# cpu.net
KiCad netlist of a schematic drawn in Altium Designer
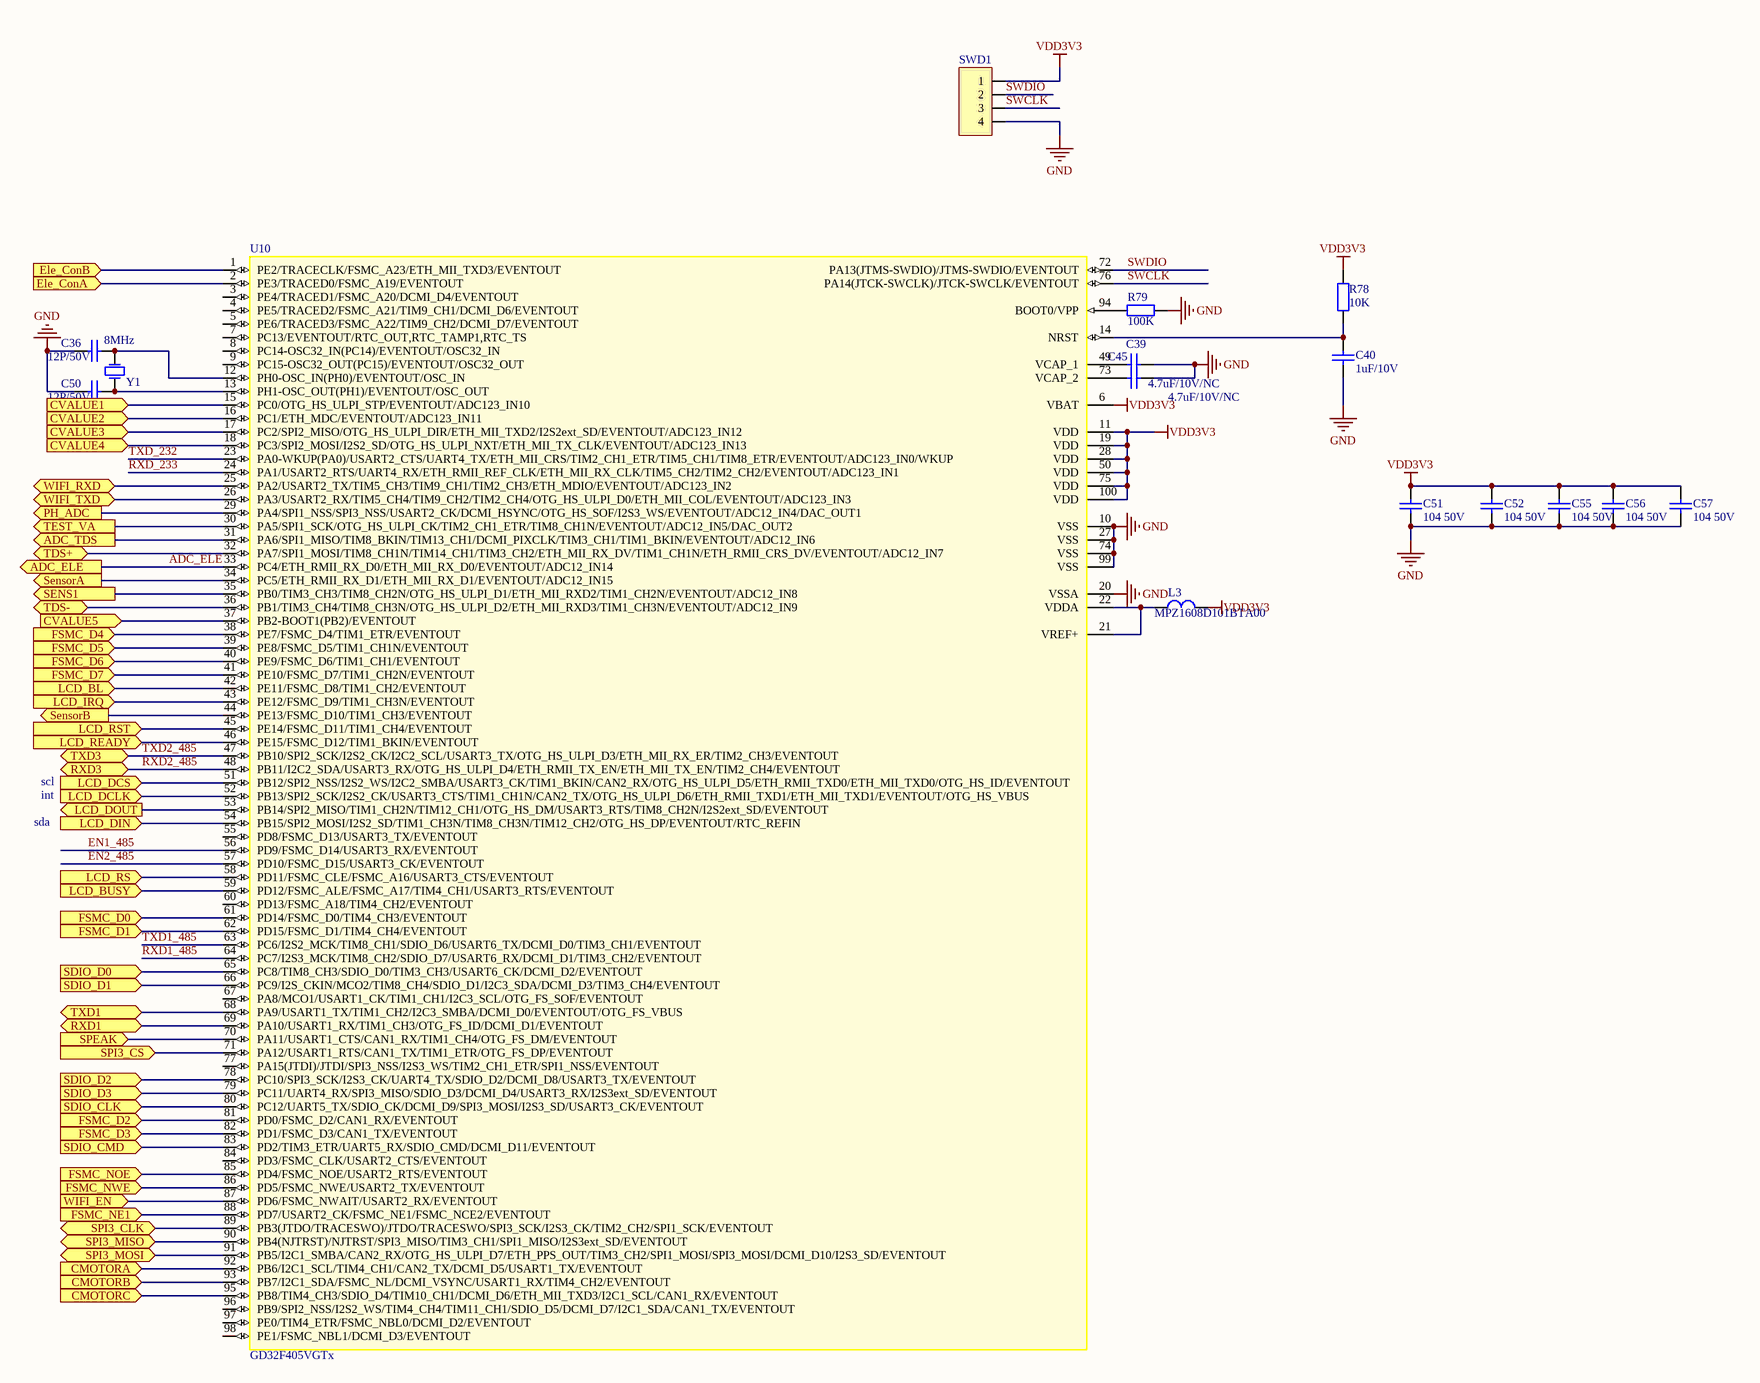
[diagram p0: cpu.SchDoc]

(export (version "E")
  (design (tool "Eeschema 10.0.6"))
  (components
    (comp (ref "C36")
      (value "12P/50V")
      (footprint "SMD-0603C")
      (description "贴片电容 5%")
      (libsource (lib "XiaoyI") (part "CAP4"))
    )
    (comp (ref "C39")
      (value "4.7uF/10V/NC")
      (footprint "SMD-0603C")
      (description "贴片电容 20%")
      (libsource (lib "XiaoyI") (part "CAP4"))
    )
    (comp (ref "C40")
      (value "1uF/10V")
      (footprint "SMD-0603C")
      (description "贴片电容 20%")
      (libsource (lib "XiaoyI") (part "CAP4"))
    )
    (comp (ref "C45")
      (value "4.7uF/10V/NC")
      (footprint "SMD-0603C")
      (description "贴片电容 20%")
      (libsource (lib "XiaoyI") (part "CAP4"))
    )
    (comp (ref "C50")
      (value "12P/50V")
      (footprint "SMD-0603C")
      (description "贴片电容 5%")
      (libsource (lib "XiaoyI") (part "CAP4"))
    )
    (comp (ref "C51")
      (value "104 50V")
      (footprint "SMD-0603C")
      (description "贴片电容 20%")
      (libsource (lib "XiaoyI") (part "CAP4"))
    )
    (comp (ref "C52")
      (value "104 50V")
      (footprint "SMD-0603C")
      (description "贴片电容 20%")
      (libsource (lib "XiaoyI") (part "CAP4"))
    )
    (comp (ref "C55")
      (value "104 50V")
      (footprint "SMD-0603C")
      (description "贴片电容 20%")
      (libsource (lib "XiaoyI") (part "CAP4"))
    )
    (comp (ref "C56")
      (value "104 50V")
      (footprint "SMD-0603C")
      (description "贴片电容 20%")
      (libsource (lib "XiaoyI") (part "CAP4"))
    )
    (comp (ref "C57")
      (value "104 50V")
      (footprint "SMD-0603C")
      (description "贴片电容 20%")
      (libsource (lib "XiaoyI") (part "CAP4"))
    )
    (comp (ref "L3")
      (value "MPZ1608D101BTA00")
      (footprint "SMD-0603")
      (description "磁珠电感 100R 100MHz")
      (libsource (lib "XiaoyI") (part "CIZHU1"))
    )
    (comp (ref "R78")
      (value "10K")
      (footprint "SMD-0603")
      (description "贴片电阻 5%")
      (libsource (lib "XiaoyI") (part "RES2"))
    )
    (comp (ref "R79")
      (value "100K")
      (footprint "SMD-0603")
      (description "贴片电阻 5%")
      (libsource (lib "") (part "RES2_1"))
    )
    (comp (ref "SWD1")
      (value "SIP-4 (NC)")
      (footprint "SIP-4")
      (description "ISP 下载")
      (libsource (lib "XiaoyI") (part "SIP-4"))
    )
    (comp (ref "U10")
      (value "GD32F405VGTx")
      (footprint "STM-LQFP100_N")
      (fields (field (name "MANUFACTURER") "STMicroelectronics") (field (name "PARTNUMBER") "STM32F405VGT6"))
      (libsource (lib "STM32F4") (part "STM32F405VGTx"))
    )
    (comp (ref "Y1")
      (value "8MHz")
      (footprint "XTAL-3225-2")
      (description "3225 贴片晶振")
      (libsource (lib "XiaoyI") (part "XTAL"))
    )
  )
  (nets
    (net (code "1") (name "/ADC_ELE") (class "Default")
      (node (ref "U10") (pin "33") (pinfunction "PC4/ETH_RMII_RX_D0/ETH_MII_RX_D0/EVENTOUT/ADC12_IN14_33") (pintype "bidirectional"))
    )
    (net (code "2") (name "/ADC_TDS") (class "Default")
      (node (ref "U10") (pin "31") (pinfunction "PA6/SPI1_MISO/TIM8_BKIN/TIM13_CH1/DCMI_PIXCLK/TIM3_CH1/TIM1_BKIN/EVENTOUT/ADC12_IN6_31") (pintype "bidirectional"))
    )
    (net (code "3") (name "/CMOTORA") (class "Default")
      (node (ref "U10") (pin "92") (pinfunction "PB6/I2C1_SCL/TIM4_CH1/CAN2_TX/DCMI_D5/USART1_TX/EVENTOUT_92") (pintype "bidirectional"))
    )
    (net (code "4") (name "/CMOTORB") (class "Default")
      (node (ref "U10") (pin "93") (pinfunction "PB7/I2C1_SDA/FSMC_NL/DCMI_VSYNC/USART1_RX/TIM4_CH2/EVENTOUT_93") (pintype "bidirectional"))
    )
    (net (code "5") (name "/CMOTORC") (class "Default")
      (node (ref "U10") (pin "95") (pinfunction "PB8/TIM4_CH3/SDIO_D4/TIM10_CH1/DCMI_D6/ETH_MII_TXD3/I2C1_SCL/CAN1_RX/EVENTOUT_95") (pintype "bidirectional"))
    )
    (net (code "6") (name "/CVALUE1") (class "Default")
      (node (ref "U10") (pin "15") (pinfunction "PC0/OTG_HS_ULPI_STP/EVENTOUT/ADC123_IN10_15") (pintype "bidirectional"))
    )
    (net (code "7") (name "/CVALUE2") (class "Default")
      (node (ref "U10") (pin "16") (pinfunction "PC1/ETH_MDC/EVENTOUT/ADC123_IN11_16") (pintype "bidirectional"))
    )
    (net (code "8") (name "/CVALUE3") (class "Default")
      (node (ref "U10") (pin "17") (pinfunction "PC2/SPI2_MISO/OTG_HS_ULPI_DIR/ETH_MII_TXD2/I2S2ext_SD/EVENTOUT/ADC123_IN12_17") (pintype "bidirectional"))
    )
    (net (code "9") (name "/CVALUE4") (class "Default")
      (node (ref "U10") (pin "18") (pinfunction "PC3/SPI2_MOSI/I2S2_SD/OTG_HS_ULPI_NXT/ETH_MII_TX_CLK/EVENTOUT/ADC123_IN13_18") (pintype "bidirectional"))
    )
    (net (code "10") (name "/CVALUE5") (class "Default")
      (node (ref "U10") (pin "37") (pinfunction "PB2-BOOT1(PB2)/EVENTOUT_37") (pintype "bidirectional"))
    )
    (net (code "11") (name "/EN1_485") (class "Default")
      (node (ref "U10") (pin "56") (pinfunction "PD9/FSMC_D14/USART3_RX/EVENTOUT_56") (pintype "bidirectional"))
    )
    (net (code "12") (name "/EN2_485") (class "Default")
      (node (ref "U10") (pin "57") (pinfunction "PD10/FSMC_D15/USART3_CK/EVENTOUT_57") (pintype "bidirectional"))
    )
    (net (code "13") (name "/Ele_ConA") (class "Default")
      (node (ref "U10") (pin "2") (pinfunction "PE3/TRACED0/FSMC_A19/EVENTOUT_2") (pintype "bidirectional"))
    )
    (net (code "14") (name "/Ele_ConB") (class "Default")
      (node (ref "U10") (pin "1") (pinfunction "PE2/TRACECLK/FSMC_A23/ETH_MII_TXD3/EVENTOUT_1") (pintype "bidirectional"))
    )
    (net (code "15") (name "/FSMC_D0") (class "Default")
      (node (ref "U10") (pin "61") (pinfunction "PD14/FSMC_D0/TIM4_CH3/EVENTOUT_61") (pintype "bidirectional"))
    )
    (net (code "16") (name "/FSMC_D1") (class "Default")
      (node (ref "U10") (pin "62") (pinfunction "PD15/FSMC_D1/TIM4_CH4/EVENTOUT_62") (pintype "bidirectional"))
    )
    (net (code "17") (name "/FSMC_D2") (class "Default")
      (node (ref "U10") (pin "81") (pinfunction "PD0/FSMC_D2/CAN1_RX/EVENTOUT_81") (pintype "bidirectional"))
    )
    (net (code "18") (name "/FSMC_D3") (class "Default")
      (node (ref "U10") (pin "82") (pinfunction "PD1/FSMC_D3/CAN1_TX/EVENTOUT_82") (pintype "bidirectional"))
    )
    (net (code "19") (name "/FSMC_D4") (class "Default")
      (node (ref "U10") (pin "38") (pinfunction "PE7/FSMC_D4/TIM1_ETR/EVENTOUT_38") (pintype "bidirectional"))
    )
    (net (code "20") (name "/FSMC_D5") (class "Default")
      (node (ref "U10") (pin "39") (pinfunction "PE8/FSMC_D5/TIM1_CH1N/EVENTOUT_39") (pintype "bidirectional"))
    )
    (net (code "21") (name "/FSMC_D6") (class "Default")
      (node (ref "U10") (pin "40") (pinfunction "PE9/FSMC_D6/TIM1_CH1/EVENTOUT_40") (pintype "bidirectional"))
    )
    (net (code "22") (name "/FSMC_D7") (class "Default")
      (node (ref "U10") (pin "41") (pinfunction "PE10/FSMC_D7/TIM1_CH2N/EVENTOUT_41") (pintype "bidirectional"))
    )
    (net (code "23") (name "/FSMC_NE1") (class "Default")
      (node (ref "U10") (pin "88") (pinfunction "PD7/USART2_CK/FSMC_NE1/FSMC_NCE2/EVENTOUT_88") (pintype "bidirectional"))
    )
    (net (code "24") (name "/FSMC_NOE") (class "Default")
      (node (ref "U10") (pin "85") (pinfunction "PD4/FSMC_NOE/USART2_RTS/EVENTOUT_85") (pintype "bidirectional"))
    )
    (net (code "25") (name "/FSMC_NWE") (class "Default")
      (node (ref "U10") (pin "86") (pinfunction "PD5/FSMC_NWE/USART2_TX/EVENTOUT_86") (pintype "bidirectional"))
    )
    (net (code "26") (name "/LCD_BL") (class "Default")
      (node (ref "U10") (pin "42") (pinfunction "PE11/FSMC_D8/TIM1_CH2/EVENTOUT_42") (pintype "bidirectional"))
    )
    (net (code "27") (name "/LCD_BUSY") (class "Default")
      (node (ref "U10") (pin "59") (pinfunction "PD12/FSMC_ALE/FSMC_A17/TIM4_CH1/USART3_RTS/EVENTOUT_59") (pintype "bidirectional"))
    )
    (net (code "28") (name "/LCD_DCLK") (class "Default")
      (node (ref "U10") (pin "52") (pinfunction "PB13/SPI2_SCK/I2S2_CK/USART3_CTS/TIM1_CH1N/CAN2_TX/OTG_HS_ULPI_D6/ETH_RMII_TXD1/ETH_MII_TXD1/EVENTOUT/OTG_HS_VBUS_52") (pintype "bidirectional"))
    )
    (net (code "29") (name "/LCD_DCS") (class "Default")
      (node (ref "U10") (pin "51") (pinfunction "PB12/SPI2_NSS/I2S2_WS/I2C2_SMBA/USART3_CK/TIM1_BKIN/CAN2_RX/OTG_HS_ULPI_D5/ETH_RMII_TXD0/ETH_MII_TXD0/OTG_HS_ID/EVENTOUT_51") (pintype "bidirectional"))
    )
    (net (code "30") (name "/LCD_DIN") (class "Default")
      (node (ref "U10") (pin "54") (pinfunction "PB15/SPI2_MOSI/I2S2_SD/TIM1_CH3N/TIM8_CH3N/TIM12_CH2/OTG_HS_DP/EVENTOUT/RTC_REFIN_54") (pintype "bidirectional"))
    )
    (net (code "31") (name "/LCD_DOUT") (class "Default")
      (node (ref "U10") (pin "53") (pinfunction "PB14/SPI2_MISO/TIM1_CH2N/TIM12_CH1/OTG_HS_DM/USART3_RTS/TIM8_CH2N/I2S2ext_SD/EVENTOUT_53") (pintype "bidirectional"))
    )
    (net (code "32") (name "/LCD_IRQ") (class "Default")
      (node (ref "U10") (pin "43") (pinfunction "PE12/FSMC_D9/TIM1_CH3N/EVENTOUT_43") (pintype "bidirectional"))
    )
    (net (code "33") (name "/LCD_READY") (class "Default")
      (node (ref "U10") (pin "46") (pinfunction "PE15/FSMC_D12/TIM1_BKIN/EVENTOUT_46") (pintype "bidirectional"))
    )
    (net (code "34") (name "/LCD_RS") (class "Default")
      (node (ref "U10") (pin "58") (pinfunction "PD11/FSMC_CLE/FSMC_A16/USART3_CTS/EVENTOUT_58") (pintype "bidirectional"))
    )
    (net (code "35") (name "/LCD_RST") (class "Default")
      (node (ref "U10") (pin "45") (pinfunction "PE14/FSMC_D11/TIM1_CH4/EVENTOUT_45") (pintype "bidirectional"))
    )
    (net (code "36") (name "/PH_ADC") (class "Default")
      (node (ref "U10") (pin "29") (pinfunction "PA4/SPI1_NSS/SPI3_NSS/USART2_CK/DCMI_HSYNC/OTG_HS_SOF/I2S3_WS/EVENTOUT/ADC12_IN4/DAC_OUT1_29") (pintype "bidirectional"))
    )
    (net (code "37") (name "/RXD1") (class "Default")
      (node (ref "U10") (pin "69") (pinfunction "PA10/USART1_RX/TIM1_CH3/OTG_FS_ID/DCMI_D1/EVENTOUT_69") (pintype "bidirectional"))
    )
    (net (code "38") (name "/RXD1_485") (class "Default")
      (node (ref "U10") (pin "64") (pinfunction "PC7/I2S3_MCK/TIM8_CH2/SDIO_D7/USART6_RX/DCMI_D1/TIM3_CH2/EVENTOUT_64") (pintype "bidirectional"))
    )
    (net (code "39") (name "/RXD2_485") (class "Default")
      (node (ref "U10") (pin "48") (pinfunction "PB11/I2C2_SDA/USART3_RX/OTG_HS_ULPI_D4/ETH_RMII_TX_EN/ETH_MII_TX_EN/TIM2_CH4/EVENTOUT_48") (pintype "bidirectional"))
    )
    (net (code "40") (name "/RXD_233") (class "Default")
      (node (ref "U10") (pin "24") (pinfunction "PA1/USART2_RTS/UART4_RX/ETH_RMII_REF_CLK/ETH_MII_RX_CLK/TIM5_CH2/TIM2_CH2/EVENTOUT/ADC123_IN1_24") (pintype "bidirectional"))
    )
    (net (code "41") (name "/SDIO_CLK") (class "Default")
      (node (ref "U10") (pin "80") (pinfunction "PC12/UART5_TX/SDIO_CK/DCMI_D9/SPI3_MOSI/I2S3_SD/USART3_CK/EVENTOUT_80") (pintype "bidirectional"))
    )
    (net (code "42") (name "/SDIO_CMD") (class "Default")
      (node (ref "U10") (pin "83") (pinfunction "PD2/TIM3_ETR/UART5_RX/SDIO_CMD/DCMI_D11/EVENTOUT_83") (pintype "bidirectional"))
    )
    (net (code "43") (name "/SDIO_D0") (class "Default")
      (node (ref "U10") (pin "65") (pinfunction "PC8/TIM8_CH3/SDIO_D0/TIM3_CH3/USART6_CK/DCMI_D2/EVENTOUT_65") (pintype "bidirectional"))
    )
    (net (code "44") (name "/SDIO_D1") (class "Default")
      (node (ref "U10") (pin "66") (pinfunction "PC9/I2S_CKIN/MCO2/TIM8_CH4/SDIO_D1/I2C3_SDA/DCMI_D3/TIM3_CH4/EVENTOUT_66") (pintype "bidirectional"))
    )
    (net (code "45") (name "/SDIO_D2") (class "Default")
      (node (ref "U10") (pin "78") (pinfunction "PC10/SPI3_SCK/I2S3_CK/UART4_TX/SDIO_D2/DCMI_D8/USART3_TX/EVENTOUT_78") (pintype "bidirectional"))
    )
    (net (code "46") (name "/SDIO_D3") (class "Default")
      (node (ref "U10") (pin "79") (pinfunction "PC11/UART4_RX/SPI3_MISO/SDIO_D3/DCMI_D4/USART3_RX/I2S3ext_SD/EVENTOUT_79") (pintype "bidirectional"))
    )
    (net (code "47") (name "/SENS1") (class "Default")
      (node (ref "U10") (pin "35") (pinfunction "PB0/TIM3_CH3/TIM8_CH2N/OTG_HS_ULPI_D1/ETH_MII_RXD2/TIM1_CH2N/EVENTOUT/ADC12_IN8_35") (pintype "bidirectional"))
    )
    (net (code "48") (name "/SPEAK") (class "Default")
      (node (ref "U10") (pin "70") (pinfunction "PA11/USART1_CTS/CAN1_RX/TIM1_CH4/OTG_FS_DM/EVENTOUT_70") (pintype "bidirectional"))
    )
    (net (code "49") (name "/SPI3_CLK") (class "Default")
      (node (ref "U10") (pin "89") (pinfunction "PB3(JTDO/TRACESWO)/JTDO/TRACESWO/SPI3_SCK/I2S3_CK/TIM2_CH2/SPI1_SCK/EVENTOUT_89") (pintype "bidirectional"))
    )
    (net (code "50") (name "/SPI3_CS") (class "Default")
      (node (ref "U10") (pin "71") (pinfunction "PA12/USART1_RTS/CAN1_TX/TIM1_ETR/OTG_FS_DP/EVENTOUT_71") (pintype "bidirectional"))
    )
    (net (code "51") (name "/SPI3_MISO") (class "Default")
      (node (ref "U10") (pin "90") (pinfunction "PB4(NJTRST)/NJTRST/SPI3_MISO/TIM3_CH1/SPI1_MISO/I2S3ext_SD/EVENTOUT_90") (pintype "bidirectional"))
    )
    (net (code "52") (name "/SPI3_MOSI") (class "Default")
      (node (ref "U10") (pin "91") (pinfunction "PB5/I2C1_SMBA/CAN2_RX/OTG_HS_ULPI_D7/ETH_PPS_OUT/TIM3_CH2/SPI1_MOSI/SPI3_MOSI/DCMI_D10/I2S3_SD/EVENTOUT_91") (pintype "bidirectional"))
    )
    (net (code "53") (name "/SWCLK") (class "Default")
      (node (ref "SWD1") (pin "3") (pinfunction "3_3") (pintype "passive"))
      (node (ref "U10") (pin "76") (pinfunction "PA14(JTCK-SWCLK)/JTCK-SWCLK/EVENTOUT_76") (pintype "bidirectional"))
    )
    (net (code "54") (name "/SWDIO") (class "Default")
      (node (ref "SWD1") (pin "2") (pinfunction "2_2") (pintype "passive"))
      (node (ref "U10") (pin "72") (pinfunction "PA13(JTMS-SWDIO)/JTMS-SWDIO/EVENTOUT_72") (pintype "bidirectional"))
    )
    (net (code "55") (name "/SensorA") (class "Default")
      (node (ref "U10") (pin "34") (pinfunction "PC5/ETH_RMII_RX_D1/ETH_MII_RX_D1/EVENTOUT/ADC12_IN15_34") (pintype "bidirectional"))
    )
    (net (code "56") (name "/SensorB") (class "Default")
      (node (ref "U10") (pin "44") (pinfunction "PE13/FSMC_D10/TIM1_CH3/EVENTOUT_44") (pintype "bidirectional"))
    )
    (net (code "57") (name "/TDS+") (class "Default")
      (node (ref "U10") (pin "32") (pinfunction "PA7/SPI1_MOSI/TIM8_CH1N/TIM14_CH1/TIM3_CH2/ETH_MII_RX_DV/TIM1_CH1N/ETH_RMII_CRS_DV/EVENTOUT/ADC12_IN7_32") (pintype "bidirectional"))
    )
    (net (code "58") (name "/TDS-") (class "Default")
      (node (ref "U10") (pin "36") (pinfunction "PB1/TIM3_CH4/TIM8_CH3N/OTG_HS_ULPI_D2/ETH_MII_RXD3/TIM1_CH3N/EVENTOUT/ADC12_IN9_36") (pintype "bidirectional"))
    )
    (net (code "59") (name "/TEST_VA") (class "Default")
      (node (ref "U10") (pin "30") (pinfunction "PA5/SPI1_SCK/OTG_HS_ULPI_CK/TIM2_CH1_ETR/TIM8_CH1N/EVENTOUT/ADC12_IN5/DAC_OUT2_30") (pintype "bidirectional"))
    )
    (net (code "60") (name "/TXD1") (class "Default")
      (node (ref "U10") (pin "68") (pinfunction "PA9/USART1_TX/TIM1_CH2/I2C3_SMBA/DCMI_D0/EVENTOUT/OTG_FS_VBUS_68") (pintype "bidirectional"))
    )
    (net (code "61") (name "/TXD1_485") (class "Default")
      (node (ref "U10") (pin "63") (pinfunction "PC6/I2S2_MCK/TIM8_CH1/SDIO_D6/USART6_TX/DCMI_D0/TIM3_CH1/EVENTOUT_63") (pintype "bidirectional"))
    )
    (net (code "62") (name "/TXD2_485") (class "Default")
      (node (ref "U10") (pin "47") (pinfunction "PB10/SPI2_SCK/I2S2_CK/I2C2_SCL/USART3_TX/OTG_HS_ULPI_D3/ETH_MII_RX_ER/TIM2_CH3/EVENTOUT_47") (pintype "bidirectional"))
    )
    (net (code "63") (name "/TXD_232") (class "Default")
      (node (ref "U10") (pin "23") (pinfunction "PA0-WKUP(PA0)/USART2_CTS/UART4_TX/ETH_MII_CRS/TIM2_CH1_ETR/TIM5_CH1/TIM8_ETR/EVENTOUT/ADC123_IN0/WKUP_23") (pintype "bidirectional"))
    )
    (net (code "64") (name "/WIFI_EN") (class "Default")
      (node (ref "U10") (pin "87") (pinfunction "PD6/FSMC_NWAIT/USART2_RX/EVENTOUT_87") (pintype "bidirectional"))
    )
    (net (code "65") (name "/WIFI_RXD") (class "Default")
      (node (ref "U10") (pin "25") (pinfunction "PA2/USART2_TX/TIM5_CH3/TIM9_CH1/TIM2_CH3/ETH_MDIO/EVENTOUT/ADC123_IN2_25") (pintype "bidirectional"))
    )
    (net (code "66") (name "/WIFI_TXD") (class "Default")
      (node (ref "U10") (pin "26") (pinfunction "PA3/USART2_RX/TIM5_CH4/TIM9_CH2/TIM2_CH4/OTG_HS_ULPI_D0/ETH_MII_COL/EVENTOUT/ADC123_IN3_26") (pintype "bidirectional"))
    )
    (net (code "67") (name "GND") (class "Default")
      (node (ref "C36") (pin "2") (pinfunction "2_2") (pintype "passive"))
      (node (ref "C39") (pin "1") (pinfunction "1_1") (pintype "passive"))
      (node (ref "C40") (pin "1") (pinfunction "1_1") (pintype "passive"))
      (node (ref "C45") (pin "1") (pinfunction "1_1") (pintype "passive"))
      (node (ref "C50") (pin "2") (pinfunction "2_2") (pintype "passive"))
      (node (ref "C51") (pin "1") (pinfunction "1_1") (pintype "passive"))
      (node (ref "C52") (pin "1") (pinfunction "1_1") (pintype "passive"))
      (node (ref "C55") (pin "1") (pinfunction "1_1") (pintype "passive"))
      (node (ref "C56") (pin "1") (pinfunction "1_1") (pintype "passive"))
      (node (ref "C57") (pin "1") (pinfunction "1_1") (pintype "passive"))
      (node (ref "R79") (pin "1") (pinfunction "1_1") (pintype "passive"))
      (node (ref "SWD1") (pin "4") (pinfunction "4_4") (pintype "passive"))
      (node (ref "U10") (pin "10") (pinfunction "VSS_10") (pintype "power_in"))
      (node (ref "U10") (pin "20") (pinfunction "VSSA_20") (pintype "power_in"))
      (node (ref "U10") (pin "27") (pinfunction "VSS_27") (pintype "power_in"))
      (node (ref "U10") (pin "74") (pinfunction "VSS_74") (pintype "power_in"))
      (node (ref "U10") (pin "99") (pinfunction "VSS_99") (pintype "power_in"))
    )
    (net (code "68") (name "Net-(U10-BOOT0{slash}VPP)") (class "Default")
      (node (ref "R79") (pin "2") (pinfunction "2_2") (pintype "passive"))
      (node (ref "U10") (pin "94") (pinfunction "BOOT0/VPP_94") (pintype "input"))
    )
    (net (code "69") (name "Net-(U10-NRST)") (class "Default")
      (node (ref "C40") (pin "2") (pinfunction "2_2") (pintype "passive"))
      (node (ref "R78") (pin "1") (pinfunction "1_1") (pintype "passive"))
      (node (ref "U10") (pin "14") (pinfunction "NRST_14") (pintype "bidirectional"))
    )
    (net (code "70") (name "Net-(U10-PH0-OSC_IN(PH0){slash}EVENTOUT{slash}OSC_IN)") (class "Default")
      (node (ref "C36") (pin "1") (pinfunction "1_1") (pintype "passive"))
      (node (ref "U10") (pin "12") (pinfunction "PH0-OSC_IN(PH0)/EVENTOUT/OSC_IN_12") (pintype "bidirectional"))
      (node (ref "Y1") (pin "2") (pinfunction "OSC2_2") (pintype "passive"))
    )
    (net (code "71") (name "Net-(U10-PH1-OSC_OUT(PH1){slash}EVENTOUT{slash}OSC_OUT)") (class "Default")
      (node (ref "C50") (pin "1") (pinfunction "1_1") (pintype "passive"))
      (node (ref "U10") (pin "13") (pinfunction "PH1-OSC_OUT(PH1)/EVENTOUT/OSC_OUT_13") (pintype "bidirectional"))
      (node (ref "Y1") (pin "1") (pinfunction "OSC1_1") (pintype "passive"))
    )
    (net (code "72") (name "Net-(U10-VCAP_1)") (class "Default")
      (node (ref "C39") (pin "2") (pinfunction "2_2") (pintype "passive"))
      (node (ref "U10") (pin "49") (pinfunction "VCAP_1_49") (pintype "power_in"))
    )
    (net (code "73") (name "Net-(U10-VCAP_2)") (class "Default")
      (node (ref "C45") (pin "2") (pinfunction "2_2") (pintype "passive"))
      (node (ref "U10") (pin "73") (pinfunction "VCAP_2_73") (pintype "power_in"))
    )
    (net (code "74") (name "Net-(U10-VDDA)") (class "Default")
      (node (ref "L3") (pin "2") (pinfunction "2_2") (pintype "passive"))
      (node (ref "U10") (pin "21") (pinfunction "VREF+_21") (pintype "power_in"))
      (node (ref "U10") (pin "22") (pinfunction "VDDA_22") (pintype "power_in"))
    )
    (net (code "75") (name "VDD3V3") (class "Default")
      (node (ref "C51") (pin "2") (pinfunction "2_2") (pintype "passive"))
      (node (ref "C52") (pin "2") (pinfunction "2_2") (pintype "passive"))
      (node (ref "C55") (pin "2") (pinfunction "2_2") (pintype "passive"))
      (node (ref "C56") (pin "2") (pinfunction "2_2") (pintype "passive"))
      (node (ref "C57") (pin "2") (pinfunction "2_2") (pintype "passive"))
      (node (ref "L3") (pin "1") (pinfunction "1_1") (pintype "passive"))
      (node (ref "R78") (pin "2") (pinfunction "2_2") (pintype "passive"))
      (node (ref "SWD1") (pin "1") (pinfunction "1_1") (pintype "passive"))
      (node (ref "U10") (pin "100") (pinfunction "VDD_100") (pintype "power_in"))
      (node (ref "U10") (pin "11") (pinfunction "VDD_11") (pintype "power_in"))
      (node (ref "U10") (pin "19") (pinfunction "VDD_19") (pintype "power_in"))
      (node (ref "U10") (pin "28") (pinfunction "VDD_28") (pintype "power_in"))
      (node (ref "U10") (pin "50") (pinfunction "VDD_50") (pintype "power_in"))
      (node (ref "U10") (pin "6") (pinfunction "VBAT_6") (pintype "power_in"))
      (node (ref "U10") (pin "75") (pinfunction "VDD_75") (pintype "power_in"))
    )
    (net (code "76") (name "unconnected-(U10-PA8{slash}MCO1{slash}USART1_CK{slash}TIM1_CH1{slash}I2C3_SCL{slash}OTG_FS_SOF{slash}EVENTOUT-Pad67)") (class "Default")
      (node (ref "U10") (pin "67") (pinfunction "PA8/MCO1/USART1_CK/TIM1_CH1/I2C3_SCL/OTG_FS_SOF/EVENTOUT_67") (pintype "bidirectional"))
    )
    (net (code "77") (name "unconnected-(U10-PA15(JTDI){slash}JTDI{slash}SPI3_NSS{slash}I2S3_WS{slash}TIM2_CH1_ETR{slash}SPI1_NSS{slash}EVENTOUT-Pad77)") (class "Default")
      (node (ref "U10") (pin "77") (pinfunction "PA15(JTDI)/JTDI/SPI3_NSS/I2S3_WS/TIM2_CH1_ETR/SPI1_NSS/EVENTOUT_77") (pintype "bidirectional"))
    )
    (net (code "78") (name "unconnected-(U10-PB9{slash}SPI2_NSS{slash}I2S2_WS{slash}TIM4_CH4{slash}TIM11_CH1{slash}SDIO_D5{slash}DCMI_D7{slash}I2C1_SDA{slash}CAN1_TX{slash}EVENTOUT-Pad96)") (class "Default")
      (node (ref "U10") (pin "96") (pinfunction "PB9/SPI2_NSS/I2S2_WS/TIM4_CH4/TIM11_CH1/SDIO_D5/DCMI_D7/I2C1_SDA/CAN1_TX/EVENTOUT_96") (pintype "bidirectional"))
    )
    (net (code "79") (name "unconnected-(U10-PC13{slash}EVENTOUT{slash}RTC_OUT,RTC_TAMP1,RTC_TS-Pad7)") (class "Default")
      (node (ref "U10") (pin "7") (pinfunction "PC13/EVENTOUT/RTC_OUT,RTC_TAMP1,RTC_TS_7") (pintype "bidirectional"))
    )
    (net (code "80") (name "unconnected-(U10-PC14-OSC32_IN(PC14){slash}EVENTOUT{slash}OSC32_IN-Pad8)") (class "Default")
      (node (ref "U10") (pin "8") (pinfunction "PC14-OSC32_IN(PC14)/EVENTOUT/OSC32_IN_8") (pintype "bidirectional"))
    )
    (net (code "81") (name "unconnected-(U10-PC15-OSC32_OUT(PC15){slash}EVENTOUT{slash}OSC32_OUT-Pad9)") (class "Default")
      (node (ref "U10") (pin "9") (pinfunction "PC15-OSC32_OUT(PC15)/EVENTOUT/OSC32_OUT_9") (pintype "bidirectional"))
    )
    (net (code "82") (name "unconnected-(U10-PD3{slash}FSMC_CLK{slash}USART2_CTS{slash}EVENTOUT-Pad84)") (class "Default")
      (node (ref "U10") (pin "84") (pinfunction "PD3/FSMC_CLK/USART2_CTS/EVENTOUT_84") (pintype "bidirectional"))
    )
    (net (code "83") (name "unconnected-(U10-PD8{slash}FSMC_D13{slash}USART3_TX{slash}EVENTOUT-Pad55)") (class "Default")
      (node (ref "U10") (pin "55") (pinfunction "PD8/FSMC_D13/USART3_TX/EVENTOUT_55") (pintype "bidirectional"))
    )
    (net (code "84") (name "unconnected-(U10-PD13{slash}FSMC_A18{slash}TIM4_CH2{slash}EVENTOUT-Pad60)") (class "Default")
      (node (ref "U10") (pin "60") (pinfunction "PD13/FSMC_A18/TIM4_CH2/EVENTOUT_60") (pintype "bidirectional"))
    )
    (net (code "85") (name "unconnected-(U10-PE0{slash}TIM4_ETR{slash}FSMC_NBL0{slash}DCMI_D2{slash}EVENTOUT-Pad97)") (class "Default")
      (node (ref "U10") (pin "97") (pinfunction "PE0/TIM4_ETR/FSMC_NBL0/DCMI_D2/EVENTOUT_97") (pintype "bidirectional"))
    )
    (net (code "86") (name "unconnected-(U10-PE1{slash}FSMC_NBL1{slash}DCMI_D3{slash}EVENTOUT-Pad98)") (class "Default")
      (node (ref "U10") (pin "98") (pinfunction "PE1/FSMC_NBL1/DCMI_D3/EVENTOUT_98") (pintype "bidirectional"))
    )
    (net (code "87") (name "unconnected-(U10-PE4{slash}TRACED1{slash}FSMC_A20{slash}DCMI_D4{slash}EVENTOUT-Pad3)") (class "Default")
      (node (ref "U10") (pin "3") (pinfunction "PE4/TRACED1/FSMC_A20/DCMI_D4/EVENTOUT_3") (pintype "bidirectional"))
    )
    (net (code "88") (name "unconnected-(U10-PE5{slash}TRACED2{slash}FSMC_A21{slash}TIM9_CH1{slash}DCMI_D6{slash}EVENTOUT-Pad4)") (class "Default")
      (node (ref "U10") (pin "4") (pinfunction "PE5/TRACED2/FSMC_A21/TIM9_CH1/DCMI_D6/EVENTOUT_4") (pintype "bidirectional"))
    )
    (net (code "89") (name "unconnected-(U10-PE6{slash}TRACED3{slash}FSMC_A22{slash}TIM9_CH2{slash}DCMI_D7{slash}EVENTOUT-Pad5)") (class "Default")
      (node (ref "U10") (pin "5") (pinfunction "PE6/TRACED3/FSMC_A22/TIM9_CH2/DCMI_D7/EVENTOUT_5") (pintype "bidirectional"))
    )
  )
)
